# potinho.net
KiCad netlist of a schematic drawn in EAGLE
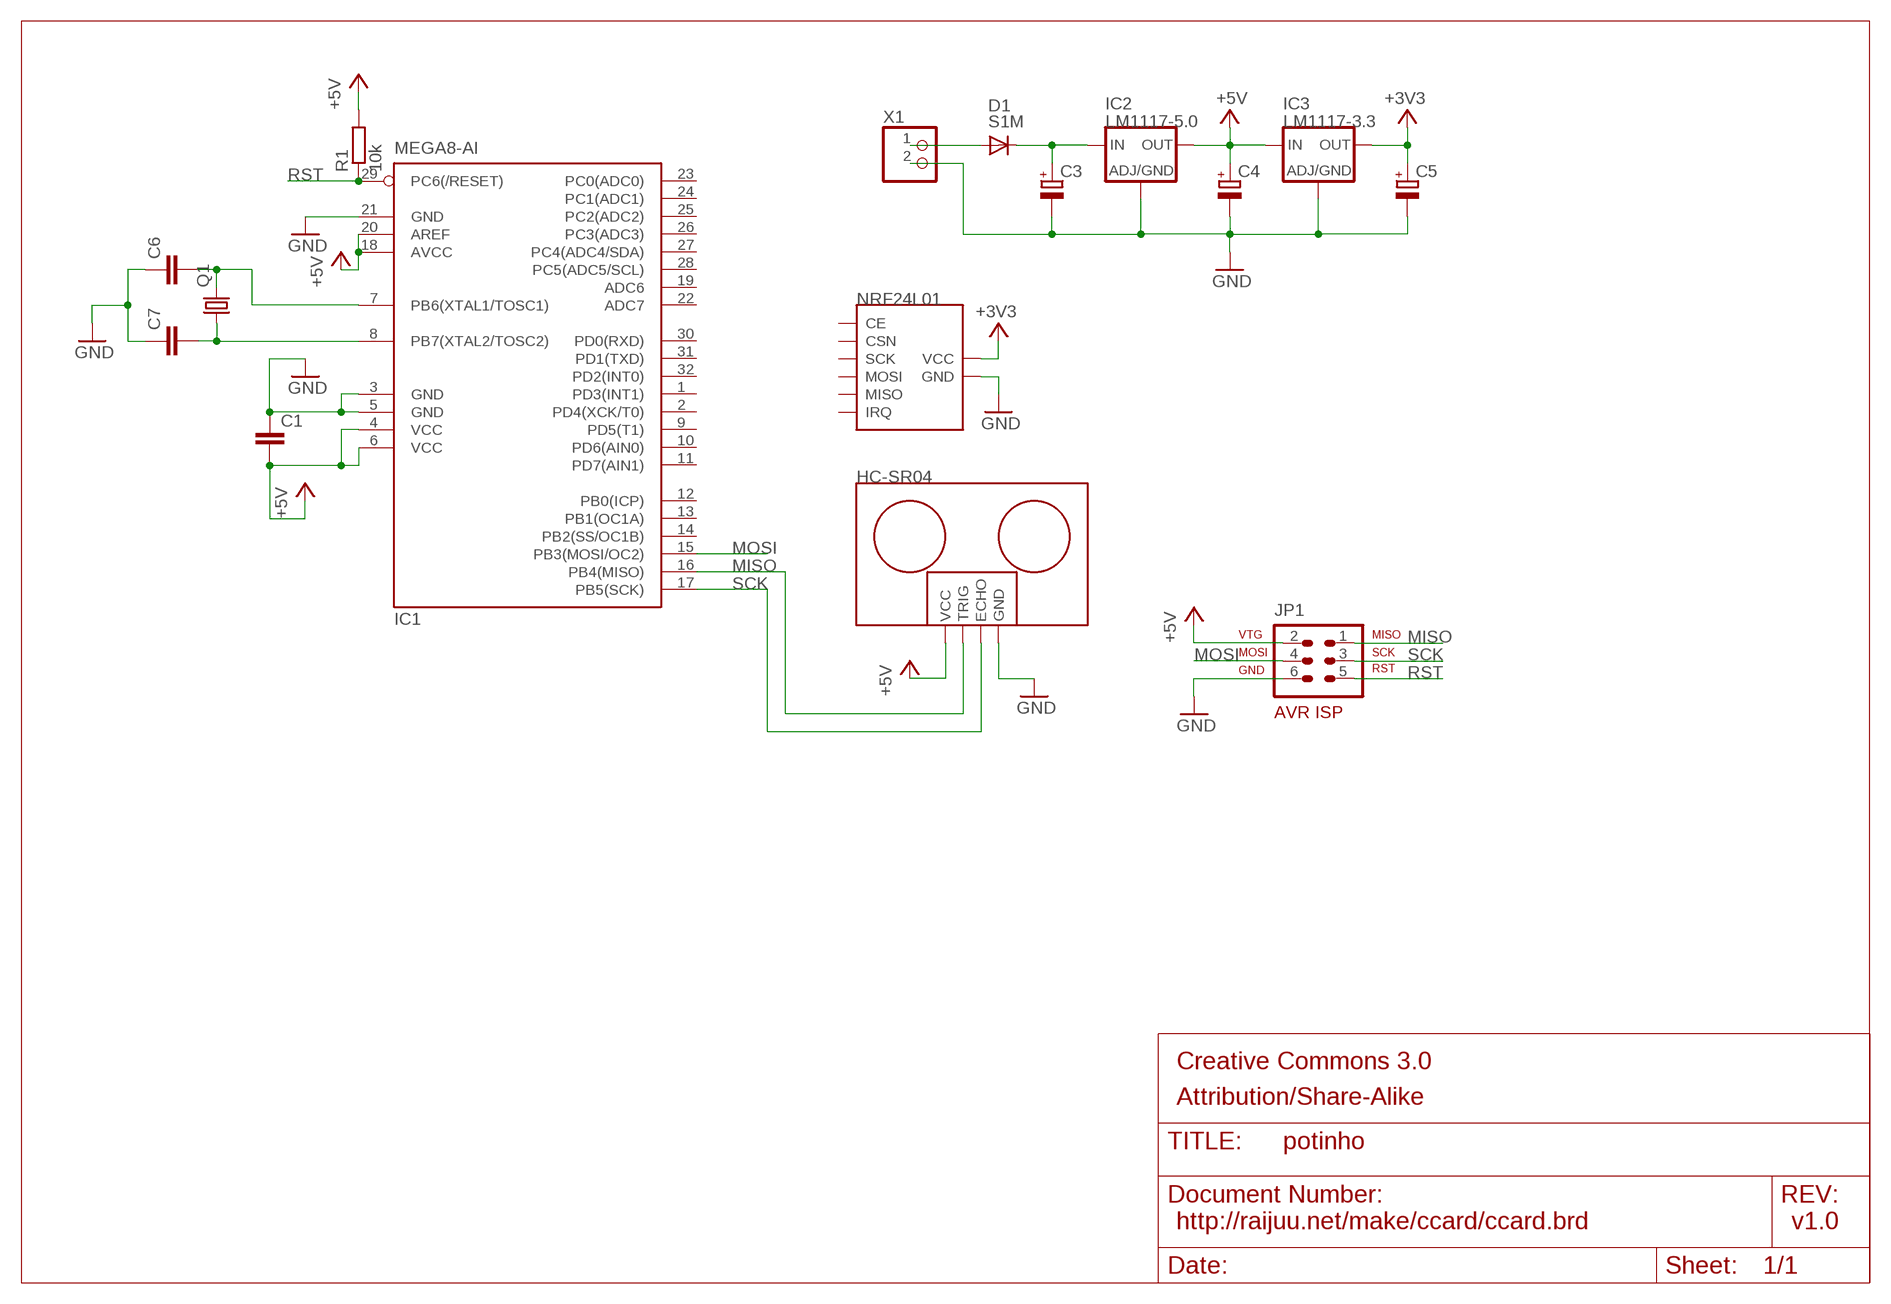
[diagram p0: schematic, sheet 1]

(export (version "E")
  (design (tool "Eeschema 10.0.6"))
  (components
    (comp (ref "C1")
      (value "C-EUC0805K")
      (footprint "eagle-import:C0805K")
      (libsource (lib "eagle-import") (part "C-EUC0805K"))
    )
    (comp (ref "C3")
      (value "CPOL-EUPD")
      (footprint "eagle-import:PANASONIC_D")
      (libsource (lib "eagle-import") (part "CPOL-EUPD"))
    )
    (comp (ref "C4")
      (value "CPOL-EUPD")
      (footprint "eagle-import:PANASONIC_D")
      (libsource (lib "eagle-import") (part "CPOL-EUPD"))
    )
    (comp (ref "C5")
      (value "CPOL-EUPD")
      (footprint "eagle-import:PANASONIC_D")
      (libsource (lib "eagle-import") (part "CPOL-EUPD"))
    )
    (comp (ref "C6")
      (value "C-EUC0805K")
      (footprint "eagle-import:C0805K")
      (libsource (lib "eagle-import") (part "C-EUC0805K"))
    )
    (comp (ref "C7")
      (value "C-EUC0805K")
      (footprint "eagle-import:C0805K")
      (libsource (lib "eagle-import") (part "C-EUC0805K"))
    )
    (comp (ref "D1")
      (value "S1M")
      (footprint "eagle-import:DO-214AC")
      (libsource (lib "eagle-import") (part "S1M"))
    )
    (comp (ref "IC1")
      (value "MEGA8-AI")
      (footprint "eagle-import:TQFP32-08")
      (fields (field (name "MPN") "ATMEGA8-16AU"))
      (libsource (lib "eagle-import") (part "MEGA8-AI"))
    )
    (comp (ref "IC2")
      (value "LM1117-5.0")
      (footprint "eagle-import:SOT223")
      (libsource (lib "eagle-import") (part "LM1117S"))
    )
    (comp (ref "IC3")
      (value "LM1117-3.3")
      (footprint "eagle-import:SOT223")
      (libsource (lib "eagle-import") (part "LM1117S"))
    )
    (comp (ref "IC4")
      (value "NRF24L01")
      (footprint "eagle-import:NRF24L01-MODULE")
      (libsource (lib "eagle-import") (part "NRF24L01-MODULE"))
    )
    (comp (ref "IC31")
      (value "HC-SR04")
      (footprint "eagle-import:1X04")
      (libsource (lib "eagle-import") (part "HC-SR04"))
    )
    (comp (ref "JP1")
      (value "AVR-ISP-6")
      (footprint "eagle-import:AVR-ISP-6")
      (libsource (lib "eagle-import") (part "AVR-ISP-6"))
    )
    (comp (ref "Q1")
      (value "CRYSTALHC49UP")
      (footprint "eagle-import:HC49UP")
      (libsource (lib "eagle-import") (part "CRYSTALHC49UP"))
    )
    (comp (ref "R1")
      (value "10k")
      (footprint "eagle-import:R0805")
      (libsource (lib "eagle-import") (part "R-EU_R0805"))
    )
    (comp (ref "X1")
      (value "W237-102")
      (footprint "eagle-import:W237-102")
      (libsource (lib "eagle-import") (part "W237-102"))
    )
  )
  (nets
    (net (code "1") (name "+3V3") (class "Default")
      (node (ref "C5") (pin "+") (pinfunction "+_+") (pintype "passive"))
      (node (ref "IC3") (pin "2") (pinfunction "OUT_2") (pintype "passive"))
      (node (ref "IC3") (pin "4") (pinfunction "OUT_4") (pintype "passive"))
      (node (ref "IC4") (pin "2") (pinfunction "VCC_2") (pintype "power_in"))
    )
    (net (code "2") (name "+5V") (class "Default")
      (node (ref "C1") (pin "2") (pinfunction "2_2") (pintype "passive"))
      (node (ref "C4") (pin "+") (pinfunction "+_+") (pintype "passive"))
      (node (ref "IC1") (pin "18") (pinfunction "AVCC_18") (pintype "power_in"))
      (node (ref "IC1") (pin "20") (pinfunction "AREF_20") (pintype "passive"))
      (node (ref "IC1") (pin "4") (pinfunction "VCC_4") (pintype "power_in"))
      (node (ref "IC1") (pin "6") (pinfunction "VCC_6") (pintype "power_in"))
      (node (ref "IC2") (pin "2") (pinfunction "OUT_2") (pintype "passive"))
      (node (ref "IC2") (pin "4") (pinfunction "OUT_4") (pintype "passive"))
      (node (ref "IC3") (pin "3") (pinfunction "IN_3") (pintype "input"))
      (node (ref "IC31") (pin "1") (pinfunction "VCC_1") (pintype "power_in"))
      (node (ref "JP1") (pin "2") (pinfunction "VTG_2") (pintype "passive"))
      (node (ref "R1") (pin "2") (pinfunction "2_2") (pintype "passive"))
    )
    (net (code "3") (name "/MISO") (class "Default")
      (node (ref "IC1") (pin "16") (pinfunction "PB4(MISO)_16") (pintype "bidirectional"))
      (node (ref "IC31") (pin "2") (pinfunction "TRIG_2") (pintype "bidirectional"))
      (node (ref "JP1") (pin "1") (pinfunction "MISO_1") (pintype "passive"))
    )
    (net (code "4") (name "/MOSI") (class "Default")
      (node (ref "IC1") (pin "15") (pinfunction "PB3(MOSI/OC2)_15") (pintype "bidirectional"))
      (node (ref "JP1") (pin "4") (pinfunction "MOSI_4") (pintype "passive"))
    )
    (net (code "5") (name "/RST") (class "Default")
      (node (ref "IC1") (pin "29") (pinfunction "PC6(/RESET)_29") (pintype "bidirectional"))
      (node (ref "JP1") (pin "5") (pinfunction "RST_5") (pintype "passive"))
      (node (ref "R1") (pin "1") (pinfunction "1_1") (pintype "passive"))
    )
    (net (code "6") (name "/SCK") (class "Default")
      (node (ref "IC1") (pin "17") (pinfunction "PB5(SCK)_17") (pintype "bidirectional"))
      (node (ref "IC31") (pin "3") (pinfunction "ECHO_3") (pintype "bidirectional"))
      (node (ref "JP1") (pin "3") (pinfunction "SCK_3") (pintype "passive"))
    )
    (net (code "7") (name "GND") (class "Default")
      (node (ref "C1") (pin "1") (pinfunction "1_1") (pintype "passive"))
      (node (ref "C3") (pin "-") (pinfunction "-_-") (pintype "passive"))
      (node (ref "C4") (pin "-") (pinfunction "-_-") (pintype "passive"))
      (node (ref "C5") (pin "-") (pinfunction "-_-") (pintype "passive"))
      (node (ref "C6") (pin "1") (pinfunction "1_1") (pintype "passive"))
      (node (ref "C7") (pin "1") (pinfunction "1_1") (pintype "passive"))
      (node (ref "IC1") (pin "21") (pinfunction "GND_21") (pintype "power_in"))
      (node (ref "IC1") (pin "3") (pinfunction "GND_3") (pintype "power_in"))
      (node (ref "IC1") (pin "5") (pinfunction "GND_5") (pintype "power_in"))
      (node (ref "IC2") (pin "1") (pinfunction "ADJ_1") (pintype "input"))
      (node (ref "IC3") (pin "1") (pinfunction "ADJ_1") (pintype "input"))
      (node (ref "IC31") (pin "4") (pinfunction "GND_4") (pintype "power_in"))
      (node (ref "IC4") (pin "1") (pinfunction "GND_1") (pintype "power_in"))
      (node (ref "JP1") (pin "6") (pinfunction "GND_6") (pintype "passive"))
      (node (ref "X1") (pin "2") (pinfunction "2_2") (pintype "passive"))
    )
    (net (code "8") (name "Net-(D1-PadA)") (class "Default")
      (node (ref "D1") (pin "A") (pinfunction "A_A") (pintype "passive"))
      (node (ref "X1") (pin "1") (pinfunction "1_1") (pintype "passive"))
    )
    (net (code "9") (name "Net-(IC1-PB6(XTAL1{slash}TOSC1))") (class "Default")
      (node (ref "C6") (pin "2") (pinfunction "2_2") (pintype "passive"))
      (node (ref "IC1") (pin "7") (pinfunction "PB6(XTAL1/TOSC1)_7") (pintype "bidirectional"))
      (node (ref "Q1") (pin "2") (pinfunction "2_2") (pintype "passive"))
    )
    (net (code "10") (name "Net-(IC1-PB7(XTAL2{slash}TOSC2))") (class "Default")
      (node (ref "C7") (pin "2") (pinfunction "2_2") (pintype "passive"))
      (node (ref "IC1") (pin "8") (pinfunction "PB7(XTAL2/TOSC2)_8") (pintype "bidirectional"))
      (node (ref "Q1") (pin "1") (pinfunction "1_1") (pintype "passive"))
    )
    (net (code "11") (name "Net-(IC2-IN)") (class "Default")
      (node (ref "C3") (pin "+") (pinfunction "+_+") (pintype "passive"))
      (node (ref "D1") (pin "C") (pinfunction "C_C") (pintype "passive"))
      (node (ref "IC2") (pin "3") (pinfunction "IN_3") (pintype "input"))
    )
    (net (code "12") (name "unconnected-(IC1-ADC6-Pad19)") (class "Default")
      (node (ref "IC1") (pin "19") (pinfunction "ADC6_19") (pintype "bidirectional"))
    )
    (net (code "13") (name "unconnected-(IC1-ADC7-Pad22)") (class "Default")
      (node (ref "IC1") (pin "22") (pinfunction "ADC7_22") (pintype "bidirectional"))
    )
    (net (code "14") (name "unconnected-(IC1-PB0(ICP)-Pad12)") (class "Default")
      (node (ref "IC1") (pin "12") (pinfunction "PB0(ICP)_12") (pintype "bidirectional"))
    )
    (net (code "15") (name "unconnected-(IC1-PB1(OC1A)-Pad13)") (class "Default")
      (node (ref "IC1") (pin "13") (pinfunction "PB1(OC1A)_13") (pintype "bidirectional"))
    )
    (net (code "16") (name "unconnected-(IC1-PB2(SS{slash}OC1B)-Pad14)") (class "Default")
      (node (ref "IC1") (pin "14") (pinfunction "PB2(SS/OC1B)_14") (pintype "bidirectional"))
    )
    (net (code "17") (name "unconnected-(IC1-PC0(ADC0)-Pad23)") (class "Default")
      (node (ref "IC1") (pin "23") (pinfunction "PC0(ADC0)_23") (pintype "bidirectional"))
    )
    (net (code "18") (name "unconnected-(IC1-PC1(ADC1)-Pad24)") (class "Default")
      (node (ref "IC1") (pin "24") (pinfunction "PC1(ADC1)_24") (pintype "bidirectional"))
    )
    (net (code "19") (name "unconnected-(IC1-PC2(ADC2)-Pad25)") (class "Default")
      (node (ref "IC1") (pin "25") (pinfunction "PC2(ADC2)_25") (pintype "bidirectional"))
    )
    (net (code "20") (name "unconnected-(IC1-PC3(ADC3)-Pad26)") (class "Default")
      (node (ref "IC1") (pin "26") (pinfunction "PC3(ADC3)_26") (pintype "bidirectional"))
    )
    (net (code "21") (name "unconnected-(IC1-PC4(ADC4{slash}SDA)-Pad27)") (class "Default")
      (node (ref "IC1") (pin "27") (pinfunction "PC4(ADC4/SDA)_27") (pintype "bidirectional"))
    )
    (net (code "22") (name "unconnected-(IC1-PC5(ADC5{slash}SCL)-Pad28)") (class "Default")
      (node (ref "IC1") (pin "28") (pinfunction "PC5(ADC5/SCL)_28") (pintype "bidirectional"))
    )
    (net (code "23") (name "unconnected-(IC1-PD0(RXD)-Pad30)") (class "Default")
      (node (ref "IC1") (pin "30") (pinfunction "PD0(RXD)_30") (pintype "bidirectional"))
    )
    (net (code "24") (name "unconnected-(IC1-PD1(TXD)-Pad31)") (class "Default")
      (node (ref "IC1") (pin "31") (pinfunction "PD1(TXD)_31") (pintype "bidirectional"))
    )
    (net (code "25") (name "unconnected-(IC1-PD2(INT0)-Pad32)") (class "Default")
      (node (ref "IC1") (pin "32") (pinfunction "PD2(INT0)_32") (pintype "bidirectional"))
    )
    (net (code "26") (name "unconnected-(IC1-PD3(INT1)-Pad1)") (class "Default")
      (node (ref "IC1") (pin "1") (pinfunction "PD3(INT1)_1") (pintype "bidirectional"))
    )
    (net (code "27") (name "unconnected-(IC1-PD4(XCK{slash}T0)-Pad2)") (class "Default")
      (node (ref "IC1") (pin "2") (pinfunction "PD4(XCK/T0)_2") (pintype "bidirectional"))
    )
    (net (code "28") (name "unconnected-(IC1-PD5(T1)-Pad9)") (class "Default")
      (node (ref "IC1") (pin "9") (pinfunction "PD5(T1)_9") (pintype "bidirectional"))
    )
    (net (code "29") (name "unconnected-(IC1-PD6(AIN0)-Pad10)") (class "Default")
      (node (ref "IC1") (pin "10") (pinfunction "PD6(AIN0)_10") (pintype "bidirectional"))
    )
    (net (code "30") (name "unconnected-(IC1-PD7(AIN1)-Pad11)") (class "Default")
      (node (ref "IC1") (pin "11") (pinfunction "PD7(AIN1)_11") (pintype "bidirectional"))
    )
    (net (code "31") (name "unconnected-(IC4-CE-Pad3)") (class "Default")
      (node (ref "IC4") (pin "3") (pinfunction "CE_3") (pintype "bidirectional"))
    )
    (net (code "32") (name "unconnected-(IC4-CSN-Pad4)") (class "Default")
      (node (ref "IC4") (pin "4") (pinfunction "CSN_4") (pintype "bidirectional"))
    )
    (net (code "33") (name "unconnected-(IC4-IRQ-Pad8)") (class "Default")
      (node (ref "IC4") (pin "8") (pinfunction "IRQ_8") (pintype "bidirectional"))
    )
    (net (code "34") (name "unconnected-(IC4-MISO-Pad7)") (class "Default")
      (node (ref "IC4") (pin "7") (pinfunction "MISO_7") (pintype "bidirectional"))
    )
    (net (code "35") (name "unconnected-(IC4-MOSI-Pad6)") (class "Default")
      (node (ref "IC4") (pin "6") (pinfunction "MOSI_6") (pintype "bidirectional"))
    )
    (net (code "36") (name "unconnected-(IC4-SCK-Pad5)") (class "Default")
      (node (ref "IC4") (pin "5") (pinfunction "SCK_5") (pintype "bidirectional"))
    )
  )
)
